# lora.net
KiCad netlist of a schematic drawn in EAGLE
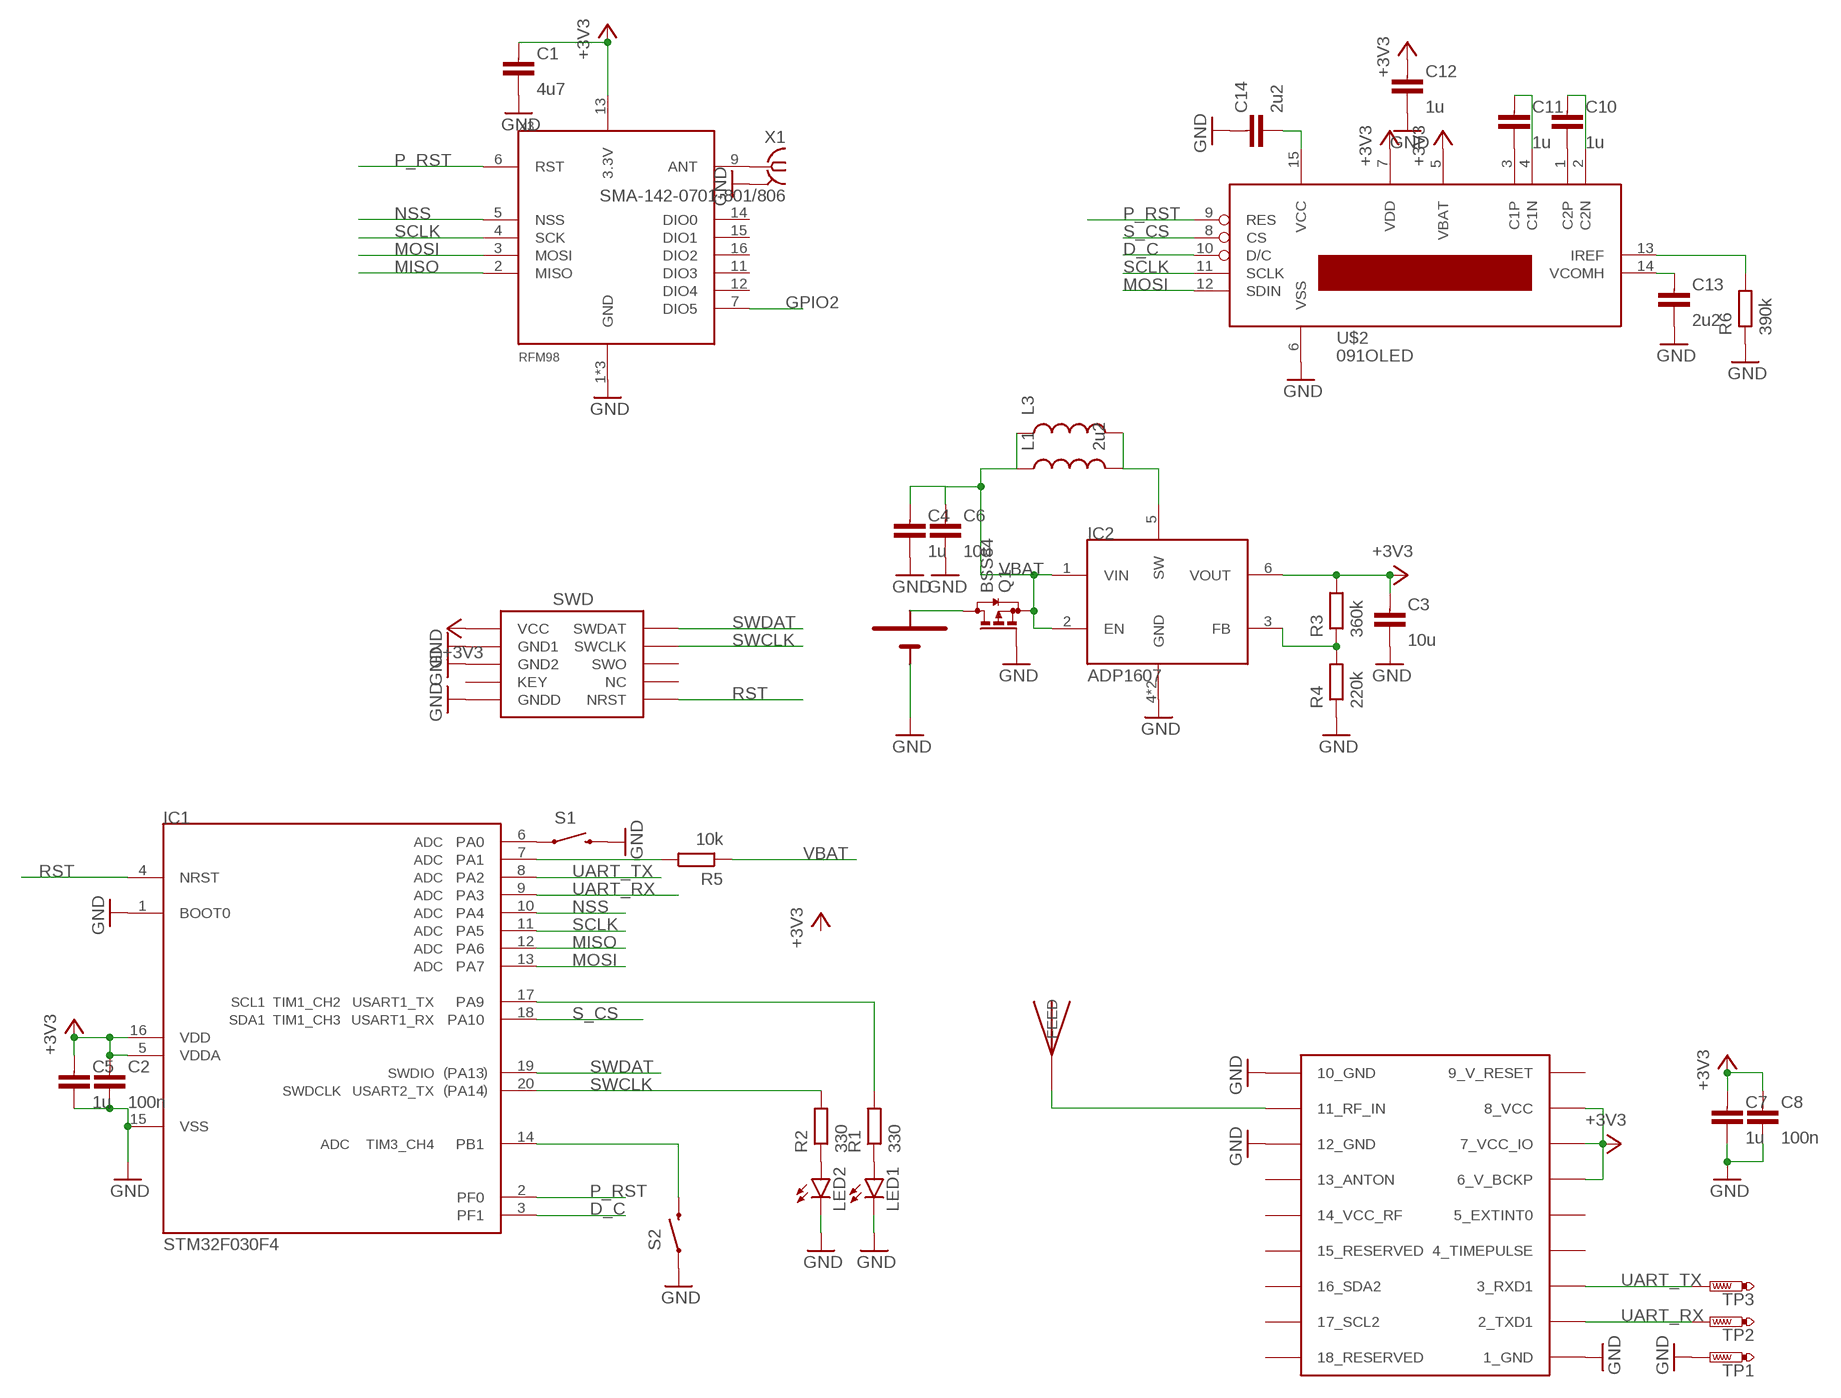
[diagram p0: schematic, sheet 1]

(export (version "E")
  (design (tool "Eeschema 10.0.6"))
  (components
    (comp (ref "C1")
      (value "4u7")
      (footprint "eagle-import:C0603-N")
      (libsource (lib "eagle-import") (part "CAPACITOR0603-N"))
    )
    (comp (ref "C2")
      (value "100n")
      (footprint "eagle-import:C0603-N")
      (libsource (lib "eagle-import") (part "CAPACITOR0603-N"))
    )
    (comp (ref "C3")
      (value "10u")
      (footprint "eagle-import:C0805-N")
      (libsource (lib "eagle-import") (part "CAPACITOR0805-N"))
    )
    (comp (ref "C4")
      (value "1u")
      (footprint "eagle-import:C0603-N")
      (libsource (lib "eagle-import") (part "CAPACITOR0603-N"))
    )
    (comp (ref "C5")
      (value "1u")
      (footprint "eagle-import:C0603-N")
      (libsource (lib "eagle-import") (part "CAPACITOR0603-N"))
    )
    (comp (ref "C6")
      (value "10u")
      (footprint "eagle-import:C0805-N")
      (libsource (lib "eagle-import") (part "CAPACITOR0805-N"))
    )
    (comp (ref "C7")
      (value "1u")
      (footprint "eagle-import:C0603-N")
      (libsource (lib "eagle-import") (part "CAPACITOR0603-N"))
    )
    (comp (ref "C8")
      (value "100n")
      (footprint "eagle-import:C0603-N")
      (libsource (lib "eagle-import") (part "CAPACITOR0603-N"))
    )
    (comp (ref "C10")
      (value "1u")
      (footprint "eagle-import:C0603-N")
      (libsource (lib "eagle-import") (part "CAPACITOR0603-N"))
    )
    (comp (ref "C11")
      (value "1u")
      (footprint "eagle-import:C0603-N")
      (libsource (lib "eagle-import") (part "CAPACITOR0603-N"))
    )
    (comp (ref "C12")
      (value "1u")
      (footprint "eagle-import:C0603-N")
      (libsource (lib "eagle-import") (part "CAPACITOR0603-N"))
    )
    (comp (ref "C13")
      (value "2u2")
      (footprint "eagle-import:C0603-N")
      (libsource (lib "eagle-import") (part "CAPACITOR0603-N"))
    )
    (comp (ref "C14")
      (value "2u2")
      (footprint "eagle-import:C0603-N")
      (libsource (lib "eagle-import") (part "CAPACITOR0603-N"))
    )
    (comp (ref "IC1")
      (value "STM32F030F4")
      (footprint "eagle-import:TSSOP20")
      (libsource (lib "eagle-import") (part "STM32F030F4"))
    )
    (comp (ref "IC2")
      (value "ADP1607")
      (footprint "eagle-import:LFCSP6")
      (libsource (lib "eagle-import") (part "ADP1607"))
    )
    (comp (ref "J1")
      (value "SWD_PTH_SHROUD")
      (footprint "eagle-import:SWD_PTH_SHROUD")
      (libsource (lib "eagle-import") (part "SWD_PTH_SHROUD"))
    )
    (comp (ref "L1")
      (value "2u2")
      (footprint "eagle-import:0805")
      (libsource (lib "eagle-import") (part "INDUCTOR0805"))
    )
    (comp (ref "L3")
      (value "INDUCTOR1210")
      (footprint "eagle-import:1210")
      (libsource (lib "eagle-import") (part "INDUCTOR1210"))
    )
    (comp (ref "LED1")
      (value "LED0603")
      (footprint "eagle-import:LED-0603")
      (libsource (lib "eagle-import") (part "LED0603"))
    )
    (comp (ref "LED2")
      (value "LED0603")
      (footprint "eagle-import:LED-0603")
      (libsource (lib "eagle-import") (part "LED0603"))
    )
    (comp (ref "Q1")
      (value "BSS84")
      (footprint "eagle-import:SOT23")
      (libsource (lib "eagle-import") (part "BSS84"))
    )
    (comp (ref "R1")
      (value "330")
      (footprint "eagle-import:R0603-N")
      (libsource (lib "eagle-import") (part "RESISTOR0603-N"))
    )
    (comp (ref "R2")
      (value "330")
      (footprint "eagle-import:R0603-N")
      (libsource (lib "eagle-import") (part "RESISTOR0603-N"))
    )
    (comp (ref "R3")
      (value "360k")
      (footprint "eagle-import:R0603-N")
      (libsource (lib "eagle-import") (part "RESISTOR0603-N"))
    )
    (comp (ref "R4")
      (value "220k")
      (footprint "eagle-import:R0603-N")
      (libsource (lib "eagle-import") (part "RESISTOR0603-N"))
    )
    (comp (ref "R5")
      (value "10k")
      (footprint "eagle-import:R0603-N")
      (libsource (lib "eagle-import") (part "RESISTOR0603-N"))
    )
    (comp (ref "R6")
      (value "390k")
      (footprint "eagle-import:R0603-N")
      (libsource (lib "eagle-import") (part "RESISTOR0603-N"))
    )
    (comp (ref "S1")
      (value "SWITCH-MOMENTARY-2SMD")
      (footprint "eagle-import:TACTILE_SWITCH_SMD")
      (libsource (lib "eagle-import") (part "SWITCH-MOMENTARY-2SMD"))
    )
    (comp (ref "S2")
      (value "SWITCH-MOMENTARY-2SMD")
      (footprint "eagle-import:TACTILE_SWITCH_SMD")
      (libsource (lib "eagle-import") (part "SWITCH-MOMENTARY-2SMD"))
    )
    (comp (ref "TP1")
      (value "PTR1B1,27")
      (footprint "eagle-import:B1,27")
      (libsource (lib "eagle-import") (part "PTR1B1,27"))
    )
    (comp (ref "TP2")
      (value "PTR1B1,27")
      (footprint "eagle-import:B1,27")
      (libsource (lib "eagle-import") (part "PTR1B1,27"))
    )
    (comp (ref "TP3")
      (value "PTR1B1,27")
      (footprint "eagle-import:B1,27")
      (libsource (lib "eagle-import") (part "PTR1B1,27"))
    )
    (comp (ref "U$2")
      (value "091OLED")
      (footprint "eagle-import:0.91OLEDCON")
      (libsource (lib "eagle-import") (part "091OLED"))
    )
    (comp (ref "U$5")
      (value "JTI_ANTENNA-1575AT43A40")
      (footprint "eagle-import:JTI_ANTENNA-1575AT43A40")
      (libsource (lib "eagle-import") (part "JTI_ANTENNA-1575AT43A40"))
    )
    (comp (ref "U$6")
      (value "KEYSTONE-92")
      (footprint "eagle-import:KEYSTONE-92-AA-BATTERY")
      (libsource (lib "eagle-import") (part "KEYSTONE-92"))
    )
    (comp (ref "X1")
      (value "SMA-142-0701-801/806")
      (footprint "eagle-import:J502-ND-142-0701-801_806")
      (fields (field (name "MF") "JOHNSON COMPONENTS") (field (name "MPN") "142-0701-801"))
      (libsource (lib "eagle-import") (part "SMA-142-0701-801/806"))
    )
    (comp (ref "X2")
      (value "UBLOX_MAX")
      (footprint "eagle-import:UBLOX_MAX")
      (libsource (lib "eagle-import") (part "UBLOX_MAX"))
    )
    (comp (ref "X3")
      (value "RFM98")
      (footprint "eagle-import:RFM97")
      (libsource (lib "eagle-import") (part "RFM98"))
    )
  )
  (nets
    (net (code "1") (name "+3V3") (class "Default")
      (node (ref "C1") (pin "1") (pinfunction "1_1") (pintype "passive"))
      (node (ref "C12") (pin "1") (pinfunction "1_1") (pintype "passive"))
      (node (ref "C2") (pin "1") (pinfunction "1_1") (pintype "passive"))
      (node (ref "C3") (pin "1") (pinfunction "1_1") (pintype "passive"))
      (node (ref "C5") (pin "1") (pinfunction "1_1") (pintype "passive"))
      (node (ref "C7") (pin "1") (pinfunction "1_1") (pintype "passive"))
      (node (ref "C8") (pin "1") (pinfunction "1_1") (pintype "passive"))
      (node (ref "IC1") (pin "16") (pinfunction "VDD_16") (pintype "power_in"))
      (node (ref "IC1") (pin "5") (pinfunction "VDDA_5") (pintype "power_in"))
      (node (ref "IC2") (pin "6") (pinfunction "VOUT_6") (pintype "output"))
      (node (ref "J1") (pin "1") (pinfunction "VCC_1") (pintype "power_in"))
      (node (ref "R3") (pin "2") (pinfunction "P$2_2") (pintype "passive"))
      (node (ref "U$2") (pin "5") (pinfunction "VBAT_5") (pintype "power_in"))
      (node (ref "U$2") (pin "7") (pinfunction "VDD_7") (pintype "power_in"))
      (node (ref "X2") (pin "6_V_BCKP") (pinfunction "6_V_BCKP_6_V_BCKP") (pintype "bidirectional"))
      (node (ref "X2") (pin "7_VCC_IO") (pinfunction "7_VCC_IO_7_VCC_IO") (pintype "power_in"))
      (node (ref "X2") (pin "8_VCC") (pinfunction "8_VCC_8_VCC") (pintype "power_in"))
      (node (ref "X3") (pin "13") (pinfunction "3.3V_13") (pintype "power_in"))
    )
    (net (code "2") (name "/9_V_RESET") (class "Default")
      (node (ref "X2") (pin "9_V_RESET") (pinfunction "9_V_RESET_9_V_RESET") (pintype "power_in"))
    )
    (net (code "3") (name "/D_C") (class "Default")
      (node (ref "IC1") (pin "3") (pinfunction "PF1_3") (pintype "bidirectional"))
      (node (ref "U$2") (pin "10") (pinfunction "D/C_10") (pintype "input"))
    )
    (net (code "4") (name "/GPIO2") (class "Default")
      (node (ref "X3") (pin "7") (pinfunction "DIO5_7") (pintype "bidirectional"))
    )
    (net (code "5") (name "/MISO") (class "Default")
      (node (ref "IC1") (pin "12") (pinfunction "PA6_12") (pintype "bidirectional"))
      (node (ref "X3") (pin "2") (pinfunction "MISO_2") (pintype "output"))
    )
    (net (code "6") (name "/MOSI") (class "Default")
      (node (ref "IC1") (pin "13") (pinfunction "PA7_13") (pintype "bidirectional"))
      (node (ref "U$2") (pin "12") (pinfunction "SDIN_12") (pintype "input"))
      (node (ref "X3") (pin "3") (pinfunction "MOSI_3") (pintype "input"))
    )
    (net (code "7") (name "/NSS") (class "Default")
      (node (ref "IC1") (pin "10") (pinfunction "PA4_10") (pintype "bidirectional"))
      (node (ref "X3") (pin "5") (pinfunction "NSS_5") (pintype "input"))
    )
    (net (code "8") (name "/P_RST") (class "Default")
      (node (ref "IC1") (pin "2") (pinfunction "PF0_2") (pintype "bidirectional"))
      (node (ref "U$2") (pin "9") (pinfunction "RES_9") (pintype "input"))
      (node (ref "X3") (pin "6") (pinfunction "RST_6") (pintype "input"))
    )
    (net (code "9") (name "/RST") (class "Default")
      (node (ref "IC1") (pin "4") (pinfunction "NRST_4") (pintype "input"))
      (node (ref "J1") (pin "10") (pinfunction "NRST_10") (pintype "bidirectional"))
    )
    (net (code "10") (name "/SCLK") (class "Default")
      (node (ref "IC1") (pin "11") (pinfunction "PA5_11") (pintype "bidirectional"))
      (node (ref "U$2") (pin "11") (pinfunction "SCLK_11") (pintype "input"))
      (node (ref "X3") (pin "4") (pinfunction "SCK_4") (pintype "input"))
    )
    (net (code "11") (name "/SWCLK") (class "Default")
      (node (ref "IC1") (pin "20") (pinfunction "PA14_20") (pintype "bidirectional"))
      (node (ref "J1") (pin "4") (pinfunction "SWCLK_4") (pintype "bidirectional"))
      (node (ref "R2") (pin "2") (pinfunction "P$2_2") (pintype "passive"))
    )
    (net (code "12") (name "/SWDAT") (class "Default")
      (node (ref "IC1") (pin "19") (pinfunction "PA13_19") (pintype "bidirectional"))
      (node (ref "J1") (pin "2") (pinfunction "SWDAT_2") (pintype "bidirectional"))
    )
    (net (code "13") (name "/S_CS") (class "Default")
      (node (ref "IC1") (pin "18") (pinfunction "PA10_18") (pintype "bidirectional"))
      (node (ref "U$2") (pin "8") (pinfunction "CS_8") (pintype "input"))
    )
    (net (code "14") (name "/UART_RX") (class "Default")
      (node (ref "IC1") (pin "9") (pinfunction "PA3_9") (pintype "bidirectional"))
      (node (ref "TP2") (pin "TP") (pinfunction "TP_TP") (pintype "input"))
      (node (ref "X2") (pin "2_TXD1") (pinfunction "2_TXD1_2_TXD1") (pintype "bidirectional"))
    )
    (net (code "15") (name "/UART_TX") (class "Default")
      (node (ref "IC1") (pin "8") (pinfunction "PA2_8") (pintype "bidirectional"))
      (node (ref "TP3") (pin "TP") (pinfunction "TP_TP") (pintype "input"))
      (node (ref "X2") (pin "3_RXD1") (pinfunction "3_RXD1_3_RXD1") (pintype "bidirectional"))
    )
    (net (code "16") (name "/VBAT") (class "Default")
      (node (ref "C4") (pin "1") (pinfunction "1_1") (pintype "passive"))
      (node (ref "C6") (pin "1") (pinfunction "1_1") (pintype "passive"))
      (node (ref "IC2") (pin "1") (pinfunction "VIN_1") (pintype "input"))
      (node (ref "IC2") (pin "2") (pinfunction "EN_2") (pintype "input"))
      (node (ref "L1") (pin "1") (pinfunction "1_1") (pintype "passive"))
      (node (ref "L3") (pin "1") (pinfunction "1_1") (pintype "passive"))
      (node (ref "Q1") (pin "2") (pinfunction "S_2") (pintype "passive"))
      (node (ref "R5") (pin "1") (pinfunction "P$1_1") (pintype "passive"))
    )
    (net (code "17") (name "GND") (class "Default")
      (node (ref "C1") (pin "2") (pinfunction "2_2") (pintype "passive"))
      (node (ref "C12") (pin "2") (pinfunction "2_2") (pintype "passive"))
      (node (ref "C13") (pin "2") (pinfunction "2_2") (pintype "passive"))
      (node (ref "C14") (pin "1") (pinfunction "1_1") (pintype "passive"))
      (node (ref "C2") (pin "2") (pinfunction "2_2") (pintype "passive"))
      (node (ref "C3") (pin "2") (pinfunction "2_2") (pintype "passive"))
      (node (ref "C4") (pin "2") (pinfunction "2_2") (pintype "passive"))
      (node (ref "C5") (pin "2") (pinfunction "2_2") (pintype "passive"))
      (node (ref "C6") (pin "2") (pinfunction "2_2") (pintype "passive"))
      (node (ref "C7") (pin "2") (pinfunction "2_2") (pintype "passive"))
      (node (ref "C8") (pin "2") (pinfunction "2_2") (pintype "passive"))
      (node (ref "IC1") (pin "1") (pinfunction "BOOT0_1") (pintype "input"))
      (node (ref "IC1") (pin "15") (pinfunction "VSS_15") (pintype "power_in"))
      (node (ref "IC2") (pin "4") (pinfunction "GND_4") (pintype "power_in"))
      (node (ref "IC2") (pin "EP") (pinfunction "GND_EP") (pintype "power_in"))
      (node (ref "J1") (pin "3") (pinfunction "GND1_3") (pintype "power_in"))
      (node (ref "J1") (pin "5") (pinfunction "GND2_5") (pintype "power_in"))
      (node (ref "J1") (pin "9") (pinfunction "GNDD_9") (pintype "power_in"))
      (node (ref "LED1") (pin "C") (pinfunction "C_C") (pintype "passive"))
      (node (ref "LED2") (pin "C") (pinfunction "C_C") (pintype "passive"))
      (node (ref "Q1") (pin "1") (pinfunction "G_1") (pintype "passive"))
      (node (ref "R4") (pin "1") (pinfunction "P$1_1") (pintype "passive"))
      (node (ref "R6") (pin "1") (pinfunction "P$1_1") (pintype "passive"))
      (node (ref "S1") (pin "3") (pinfunction "2_3") (pintype "passive"))
      (node (ref "S2") (pin "1") (pinfunction "1_1") (pintype "passive"))
      (node (ref "TP1") (pin "TP") (pinfunction "TP_TP") (pintype "input"))
      (node (ref "U$2") (pin "6") (pinfunction "VSS_6") (pintype "power_in"))
      (node (ref "U$6") (pin "GND") (pinfunction "-_GND") (pintype "passive"))
      (node (ref "U$6") (pin "GND2") (pinfunction "-_GND2") (pintype "passive"))
      (node (ref "X1") (pin "G@1") (pinfunction "2_G@1") (pintype "passive"))
      (node (ref "X1") (pin "G@2") (pinfunction "2_G@2") (pintype "passive"))
      (node (ref "X1") (pin "G@3") (pinfunction "2_G@3") (pintype "passive"))
      (node (ref "X1") (pin "G@4") (pinfunction "2_G@4") (pintype "passive"))
      (node (ref "X2") (pin "10_GND") (pinfunction "10_GND_10_GND") (pintype "power_in"))
      (node (ref "X2") (pin "12_GND") (pinfunction "12_GND_12_GND") (pintype "power_in"))
      (node (ref "X2") (pin "1_GND") (pinfunction "1_GND_1_GND") (pintype "power_in"))
      (node (ref "X3") (pin "1") (pinfunction "GND_1") (pintype "power_in"))
      (node (ref "X3") (pin "10") (pinfunction "GND_10") (pintype "power_in"))
      (node (ref "X3") (pin "8") (pinfunction "GND_8") (pintype "power_in"))
    )
    (net (code "18") (name "Net-(IC1-PA0)") (class "Default")
      (node (ref "IC1") (pin "6") (pinfunction "PA0_6") (pintype "bidirectional"))
      (node (ref "S1") (pin "1") (pinfunction "1_1") (pintype "passive"))
    )
    (net (code "19") (name "Net-(IC1-PA1)") (class "Default")
      (node (ref "IC1") (pin "7") (pinfunction "PA1_7") (pintype "bidirectional"))
      (node (ref "R5") (pin "2") (pinfunction "P$2_2") (pintype "passive"))
    )
    (net (code "20") (name "Net-(IC1-PA9)") (class "Default")
      (node (ref "IC1") (pin "17") (pinfunction "PA9_17") (pintype "bidirectional"))
      (node (ref "R1") (pin "2") (pinfunction "P$2_2") (pintype "passive"))
    )
    (net (code "21") (name "Net-(IC1-PB1)") (class "Default")
      (node (ref "IC1") (pin "14") (pinfunction "PB1_14") (pintype "bidirectional"))
      (node (ref "S2") (pin "3") (pinfunction "2_3") (pintype "passive"))
    )
    (net (code "22") (name "Net-(IC2-FB)") (class "Default")
      (node (ref "IC2") (pin "3") (pinfunction "FB_3") (pintype "input"))
      (node (ref "R3") (pin "1") (pinfunction "P$1_1") (pintype "passive"))
      (node (ref "R4") (pin "2") (pinfunction "P$2_2") (pintype "passive"))
    )
    (net (code "23") (name "Net-(IC2-SW)") (class "Default")
      (node (ref "IC2") (pin "5") (pinfunction "SW_5") (pintype "input"))
      (node (ref "L1") (pin "2") (pinfunction "2_2") (pintype "passive"))
      (node (ref "L3") (pin "2") (pinfunction "2_2") (pintype "passive"))
    )
    (net (code "24") (name "Net-(Q1-D)") (class "Default")
      (node (ref "Q1") (pin "3") (pinfunction "D_3") (pintype "passive"))
      (node (ref "U$6") (pin "VBATT") (pinfunction "+_VBATT") (pintype "passive"))
      (node (ref "U$6") (pin "VBATT1") (pinfunction "+_VBATT1") (pintype "passive"))
    )
    (net (code "25") (name "Net-(R1-P$1)") (class "Default")
      (node (ref "LED1") (pin "A") (pinfunction "A_A") (pintype "passive"))
      (node (ref "R1") (pin "1") (pinfunction "P$1_1") (pintype "passive"))
    )
    (net (code "26") (name "Net-(R2-P$1)") (class "Default")
      (node (ref "LED2") (pin "A") (pinfunction "A_A") (pintype "passive"))
      (node (ref "R2") (pin "1") (pinfunction "P$1_1") (pintype "passive"))
    )
    (net (code "27") (name "Net-(R6-P$2)") (class "Default")
      (node (ref "R6") (pin "2") (pinfunction "P$2_2") (pintype "passive"))
      (node (ref "U$2") (pin "13") (pinfunction "IREF_13") (pintype "input"))
    )
    (net (code "28") (name "Net-(U$2-C1N)") (class "Default")
      (node (ref "C11") (pin "1") (pinfunction "1_1") (pintype "passive"))
      (node (ref "U$2") (pin "4") (pinfunction "C1N_4") (pintype "bidirectional"))
    )
    (net (code "29") (name "Net-(U$2-C1P)") (class "Default")
      (node (ref "C11") (pin "2") (pinfunction "2_2") (pintype "passive"))
      (node (ref "U$2") (pin "3") (pinfunction "C1P_3") (pintype "bidirectional"))
    )
    (net (code "30") (name "Net-(U$2-C2N)") (class "Default")
      (node (ref "C10") (pin "1") (pinfunction "1_1") (pintype "passive"))
      (node (ref "U$2") (pin "2") (pinfunction "C2N_2") (pintype "bidirectional"))
    )
    (net (code "31") (name "Net-(U$2-C2P)") (class "Default")
      (node (ref "C10") (pin "2") (pinfunction "2_2") (pintype "passive"))
      (node (ref "U$2") (pin "1") (pinfunction "C2P_1") (pintype "bidirectional"))
    )
    (net (code "32") (name "Net-(U$2-VCC)") (class "Default")
      (node (ref "C14") (pin "2") (pinfunction "2_2") (pintype "passive"))
      (node (ref "U$2") (pin "15") (pinfunction "VCC_15") (pintype "power_in"))
    )
    (net (code "33") (name "Net-(U$2-VCOMH)") (class "Default")
      (node (ref "C13") (pin "1") (pinfunction "1_1") (pintype "passive"))
      (node (ref "U$2") (pin "14") (pinfunction "VCOMH_14") (pintype "output"))
    )
    (net (code "34") (name "Net-(U$5-PadFEED)") (class "Default")
      (node (ref "U$5") (pin "FEED") (pinfunction "FEED_FEED") (pintype "bidirectional"))
      (node (ref "X2") (pin "11_RF_IN") (pinfunction "11_RF_IN_11_RF_IN") (pintype "bidirectional"))
    )
    (net (code "35") (name "Net-(X3-ANT)") (class "Default")
      (node (ref "X1") (pin "1") (pinfunction "1_1") (pintype "passive"))
      (node (ref "X3") (pin "9") (pinfunction "ANT_9") (pintype "bidirectional"))
    )
    (net (code "36") (name "unconnected-(J1-KEY-Pad7)") (class "Default")
      (node (ref "J1") (pin "7") (pinfunction "KEY_7") (pintype "bidirectional"))
    )
    (net (code "37") (name "unconnected-(J1-NC-Pad8)") (class "Default")
      (node (ref "J1") (pin "8") (pinfunction "NC_8") (pintype "no_connect"))
    )
    (net (code "38") (name "unconnected-(J1-SWO-Pad6)") (class "Default")
      (node (ref "J1") (pin "6") (pinfunction "SWO_6") (pintype "bidirectional"))
    )
    (net (code "39") (name "unconnected-(X2-Pad4_TIMEPULSE)") (class "Default")
      (node (ref "X2") (pin "4_TIMEPULSE") (pinfunction "4_TIMEPULSE_4_TIMEPULSE") (pintype "bidirectional"))
    )
    (net (code "40") (name "unconnected-(X2-Pad5_EXTINT0)") (class "Default")
      (node (ref "X2") (pin "5_EXTINT0") (pinfunction "5_EXTINT0_5_EXTINT0") (pintype "bidirectional"))
    )
    (net (code "41") (name "unconnected-(X2-Pad13_ANTON)") (class "Default")
      (node (ref "X2") (pin "13_ANTON") (pinfunction "13_ANTON_13_ANTON") (pintype "bidirectional"))
    )
    (net (code "42") (name "unconnected-(X2-Pad14_VCC_RF)") (class "Default")
      (node (ref "X2") (pin "14_VCC_RF") (pinfunction "14_VCC_RF_14_VCC_RF") (pintype "bidirectional"))
    )
    (net (code "43") (name "unconnected-(X2-Pad15_RESERVED)") (class "Default")
      (node (ref "X2") (pin "15_RESERVED") (pinfunction "15_RESERVED_15_RESERVED") (pintype "bidirectional"))
    )
    (net (code "44") (name "unconnected-(X2-Pad16_SDA2)") (class "Default")
      (node (ref "X2") (pin "16_SDA2") (pinfunction "16_SDA2_16_SDA2") (pintype "bidirectional"))
    )
    (net (code "45") (name "unconnected-(X2-Pad17_SCL2)") (class "Default")
      (node (ref "X2") (pin "17_SCL2") (pinfunction "17_SCL2_17_SCL2") (pintype "bidirectional"))
    )
    (net (code "46") (name "unconnected-(X2-Pad18_RESERVED)") (class "Default")
      (node (ref "X2") (pin "18_RESERVED") (pinfunction "18_RESERVED_18_RESERVED") (pintype "bidirectional"))
    )
    (net (code "47") (name "unconnected-(X3-DIO0-Pad14)") (class "Default")
      (node (ref "X3") (pin "14") (pinfunction "DIO0_14") (pintype "bidirectional"))
    )
    (net (code "48") (name "unconnected-(X3-DIO1-Pad15)") (class "Default")
      (node (ref "X3") (pin "15") (pinfunction "DIO1_15") (pintype "bidirectional"))
    )
    (net (code "49") (name "unconnected-(X3-DIO2-Pad16)") (class "Default")
      (node (ref "X3") (pin "16") (pinfunction "DIO2_16") (pintype "bidirectional"))
    )
    (net (code "50") (name "unconnected-(X3-DIO3-Pad11)") (class "Default")
      (node (ref "X3") (pin "11") (pinfunction "DIO3_11") (pintype "bidirectional"))
    )
    (net (code "51") (name "unconnected-(X3-DIO4-Pad12)") (class "Default")
      (node (ref "X3") (pin "12") (pinfunction "DIO4_12") (pintype "bidirectional"))
    )
  )
)
